# multipreamp-1.net
KiCad netlist of a schematic drawn in EAGLE
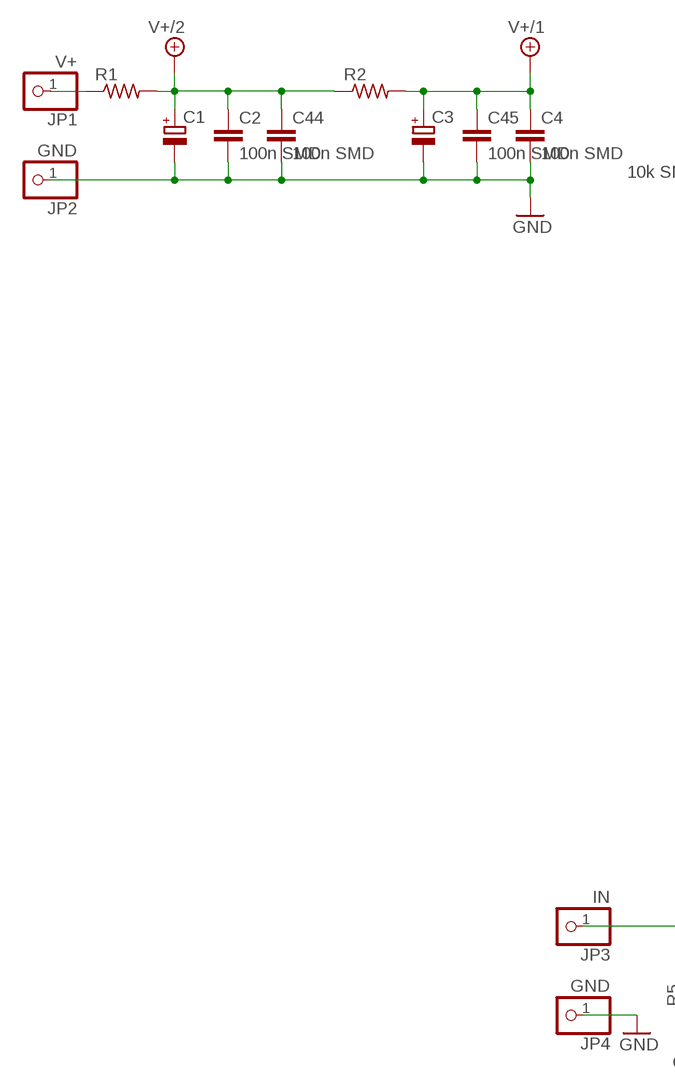
[diagram p0: schematic, sheet 1, part 1 of 2]
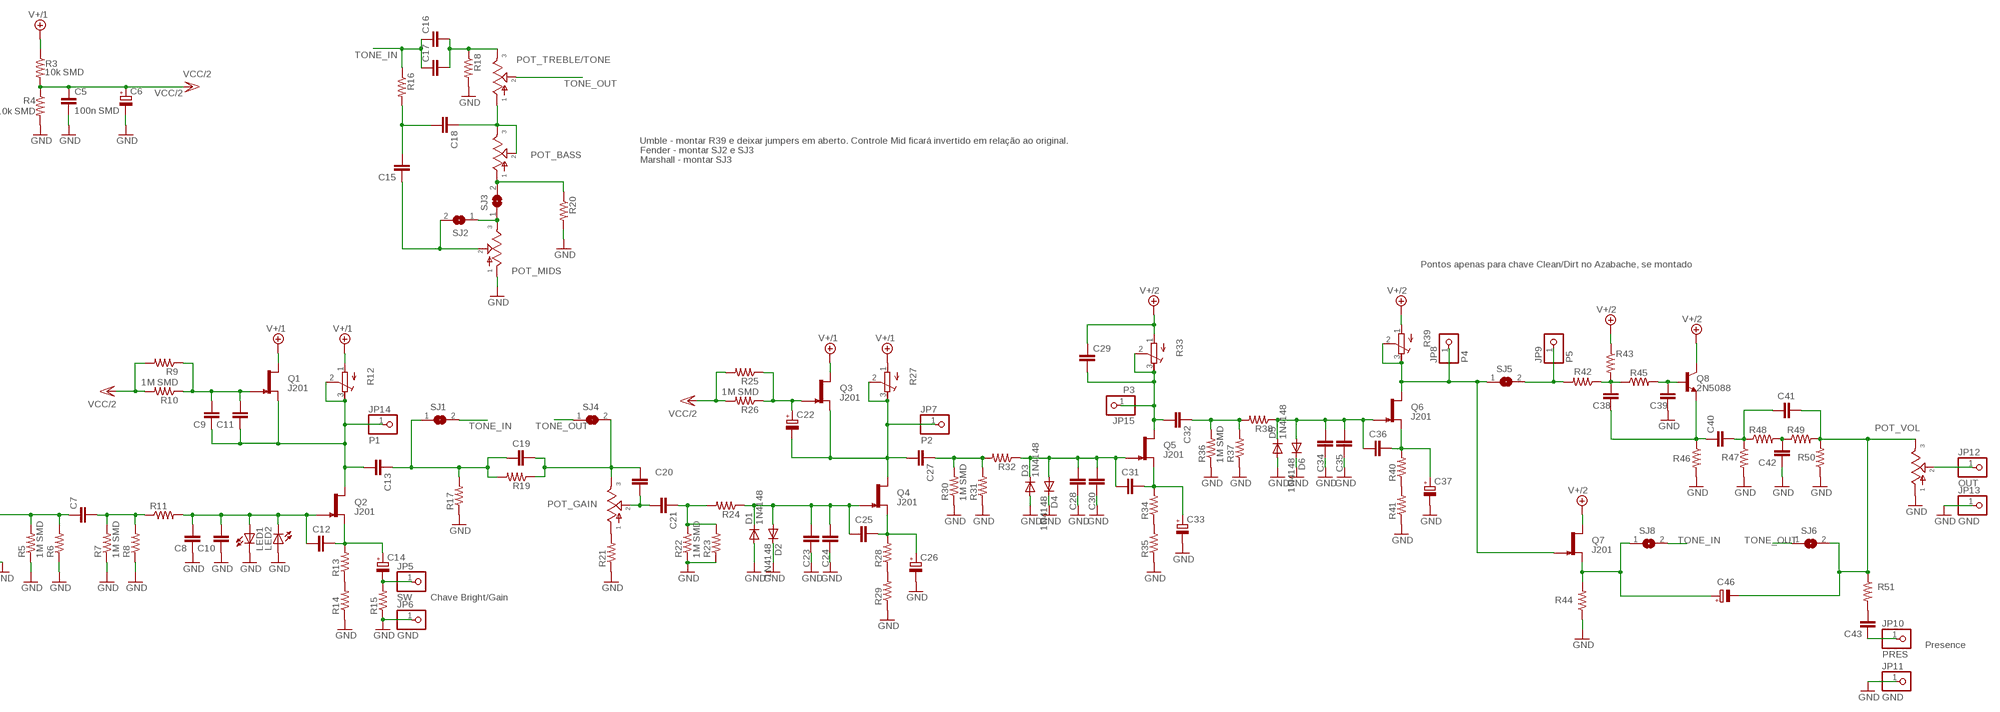
[diagram p1: schematic, sheet 1, part 2 of 2]

(export (version "E")
  (design (tool "Eeschema 10.0.6"))
  (components
    (comp (ref "C1")
      (value "CPOL-EUE2.5-6")
      (footprint "eagle-import:E2,5-6")
      (libsource (lib "eagle-import") (part "CPOL-EUE2.5-6"))
    )
    (comp (ref "C2")
      (value "100n SMD")
      (footprint "eagle-import:C0805")
      (libsource (lib "eagle-import") (part "C-EUC0805"))
    )
    (comp (ref "C3")
      (value "CPOL-EUE2.5-6")
      (footprint "eagle-import:E2,5-6")
      (libsource (lib "eagle-import") (part "CPOL-EUE2.5-6"))
    )
    (comp (ref "C4")
      (value "100n SMD")
      (footprint "eagle-import:C0805")
      (libsource (lib "eagle-import") (part "C-EUC0805"))
    )
    (comp (ref "C5")
      (value "100n SMD")
      (footprint "eagle-import:C0805")
      (libsource (lib "eagle-import") (part "C-EUC0805"))
    )
    (comp (ref "C6")
      (value "CPOL-EUE2.5-6")
      (footprint "eagle-import:E2,5-6")
      (libsource (lib "eagle-import") (part "CPOL-EUE2.5-6"))
    )
    (comp (ref "C7")
      (value "C-EU050-025X075")
      (footprint "eagle-import:C050-025X075")
      (libsource (lib "eagle-import") (part "C-EU050-025X075"))
    )
    (comp (ref "C8")
      (value "C-EU025-025X050")
      (footprint "eagle-import:C025-025X050")
      (libsource (lib "eagle-import") (part "C-EU025-025X050"))
    )
    (comp (ref "C9")
      (value "C-EU025-025X050")
      (footprint "eagle-import:C025-025X050")
      (libsource (lib "eagle-import") (part "C-EU025-025X050"))
    )
    (comp (ref "C10")
      (value "C-EU025-025X050")
      (footprint "eagle-import:C025-025X050")
      (libsource (lib "eagle-import") (part "C-EU025-025X050"))
    )
    (comp (ref "C11")
      (value "C-EU025-025X050")
      (footprint "eagle-import:C025-025X050")
      (libsource (lib "eagle-import") (part "C-EU025-025X050"))
    )
    (comp (ref "C12")
      (value "C-EU025-025X050")
      (footprint "eagle-import:C025-025X050")
      (libsource (lib "eagle-import") (part "C-EU025-025X050"))
    )
    (comp (ref "C13")
      (value "C-EU050-025X075")
      (footprint "eagle-import:C050-025X075")
      (libsource (lib "eagle-import") (part "C-EU050-025X075"))
    )
    (comp (ref "C14")
      (value "CPOL-EUE2.5-6")
      (footprint "eagle-import:E2,5-6")
      (libsource (lib "eagle-import") (part "CPOL-EUE2.5-6"))
    )
    (comp (ref "C15")
      (value "C-EU050-025X075")
      (footprint "eagle-import:C050-025X075")
      (libsource (lib "eagle-import") (part "C-EU050-025X075"))
    )
    (comp (ref "C16")
      (value "C-EU025-025X050")
      (footprint "eagle-import:C025-025X050")
      (libsource (lib "eagle-import") (part "C-EU025-025X050"))
    )
    (comp (ref "C17")
      (value "C-EU025-025X050")
      (footprint "eagle-import:C025-025X050")
      (libsource (lib "eagle-import") (part "C-EU025-025X050"))
    )
    (comp (ref "C18")
      (value "C-EU050-025X075")
      (footprint "eagle-import:C050-025X075")
      (libsource (lib "eagle-import") (part "C-EU050-025X075"))
    )
    (comp (ref "C19")
      (value "C-EU050-025X075")
      (footprint "eagle-import:C050-025X075")
      (libsource (lib "eagle-import") (part "C-EU050-025X075"))
    )
    (comp (ref "C20")
      (value "C-EU025-025X050")
      (footprint "eagle-import:C025-025X050")
      (libsource (lib "eagle-import") (part "C-EU025-025X050"))
    )
    (comp (ref "C21")
      (value "C-EU050-025X075")
      (footprint "eagle-import:C050-025X075")
      (libsource (lib "eagle-import") (part "C-EU050-025X075"))
    )
    (comp (ref "C22")
      (value "CPOL-EUE2.5-6")
      (footprint "eagle-import:E2,5-6")
      (libsource (lib "eagle-import") (part "CPOL-EUE2.5-6"))
    )
    (comp (ref "C23")
      (value "C-EU025-025X050")
      (footprint "eagle-import:C025-025X050")
      (libsource (lib "eagle-import") (part "C-EU025-025X050"))
    )
    (comp (ref "C24")
      (value "C-EU025-025X050")
      (footprint "eagle-import:C025-025X050")
      (libsource (lib "eagle-import") (part "C-EU025-025X050"))
    )
    (comp (ref "C25")
      (value "C-EU025-025X050")
      (footprint "eagle-import:C025-025X050")
      (libsource (lib "eagle-import") (part "C-EU025-025X050"))
    )
    (comp (ref "C26")
      (value "CPOL-EUE2.5-6")
      (footprint "eagle-import:E2,5-6")
      (libsource (lib "eagle-import") (part "CPOL-EUE2.5-6"))
    )
    (comp (ref "C27")
      (value "C-EU050-025X075")
      (footprint "eagle-import:C050-025X075")
      (libsource (lib "eagle-import") (part "C-EU050-025X075"))
    )
    (comp (ref "C28")
      (value "C-EU025-025X050")
      (footprint "eagle-import:C025-025X050")
      (libsource (lib "eagle-import") (part "C-EU025-025X050"))
    )
    (comp (ref "C29")
      (value "C-EU050-025X075")
      (footprint "eagle-import:C050-025X075")
      (libsource (lib "eagle-import") (part "C-EU050-025X075"))
    )
    (comp (ref "C30")
      (value "C-EU025-025X050")
      (footprint "eagle-import:C025-025X050")
      (libsource (lib "eagle-import") (part "C-EU025-025X050"))
    )
    (comp (ref "C31")
      (value "C-EU025-025X050")
      (footprint "eagle-import:C025-025X050")
      (libsource (lib "eagle-import") (part "C-EU025-025X050"))
    )
    (comp (ref "C32")
      (value "C-EU050-025X075")
      (footprint "eagle-import:C050-025X075")
      (libsource (lib "eagle-import") (part "C-EU050-025X075"))
    )
    (comp (ref "C33")
      (value "CPOL-EUE2.5-6")
      (footprint "eagle-import:E2,5-6")
      (libsource (lib "eagle-import") (part "CPOL-EUE2.5-6"))
    )
    (comp (ref "C34")
      (value "C-EU025-025X050")
      (footprint "eagle-import:C025-025X050")
      (libsource (lib "eagle-import") (part "C-EU025-025X050"))
    )
    (comp (ref "C35")
      (value "C-EU025-025X050")
      (footprint "eagle-import:C025-025X050")
      (libsource (lib "eagle-import") (part "C-EU025-025X050"))
    )
    (comp (ref "C36")
      (value "C-EU025-025X050")
      (footprint "eagle-import:C025-025X050")
      (libsource (lib "eagle-import") (part "C-EU025-025X050"))
    )
    (comp (ref "C37")
      (value "CPOL-EUE2.5-6")
      (footprint "eagle-import:E2,5-6")
      (libsource (lib "eagle-import") (part "CPOL-EUE2.5-6"))
    )
    (comp (ref "C38")
      (value "C-EU050-025X075")
      (footprint "eagle-import:C050-025X075")
      (libsource (lib "eagle-import") (part "C-EU050-025X075"))
    )
    (comp (ref "C39")
      (value "C-EU025-025X050")
      (footprint "eagle-import:C025-025X050")
      (libsource (lib "eagle-import") (part "C-EU025-025X050"))
    )
    (comp (ref "C40")
      (value "C-EU050-025X075")
      (footprint "eagle-import:C050-025X075")
      (libsource (lib "eagle-import") (part "C-EU050-025X075"))
    )
    (comp (ref "C41")
      (value "C-EU050-025X075")
      (footprint "eagle-import:C050-025X075")
      (libsource (lib "eagle-import") (part "C-EU050-025X075"))
    )
    (comp (ref "C42")
      (value "C-EU050-025X075")
      (footprint "eagle-import:C050-025X075")
      (libsource (lib "eagle-import") (part "C-EU050-025X075"))
    )
    (comp (ref "C43")
      (value "C-EU050-025X075")
      (footprint "eagle-import:C050-025X075")
      (libsource (lib "eagle-import") (part "C-EU050-025X075"))
    )
    (comp (ref "C44")
      (value "100n SMD")
      (footprint "eagle-import:C0805")
      (libsource (lib "eagle-import") (part "C-EUC0805"))
    )
    (comp (ref "C45")
      (value "100n SMD")
      (footprint "eagle-import:C0805")
      (libsource (lib "eagle-import") (part "C-EUC0805"))
    )
    (comp (ref "C46")
      (value "CPOL-EUE2.5-6")
      (footprint "eagle-import:E2,5-6")
      (libsource (lib "eagle-import") (part "CPOL-EUE2.5-6"))
    )
    (comp (ref "D1")
      (value "1N4148")
      (footprint "eagle-import:DO35-7")
      (libsource (lib "eagle-import") (part "1N4148DO35-7"))
    )
    (comp (ref "D2")
      (value "1N4148")
      (footprint "eagle-import:DO35-7")
      (libsource (lib "eagle-import") (part "1N4148DO35-7"))
    )
    (comp (ref "D3")
      (value "1N4148")
      (footprint "eagle-import:DO35-7")
      (libsource (lib "eagle-import") (part "1N4148DO35-7"))
    )
    (comp (ref "D4")
      (value "1N4148")
      (footprint "eagle-import:DO35-7")
      (libsource (lib "eagle-import") (part "1N4148DO35-7"))
    )
    (comp (ref "D5")
      (value "1N4148")
      (footprint "eagle-import:DO35-7")
      (libsource (lib "eagle-import") (part "1N4148DO35-7"))
    )
    (comp (ref "D6")
      (value "1N4148")
      (footprint "eagle-import:DO35-7")
      (libsource (lib "eagle-import") (part "1N4148DO35-7"))
    )
    (comp (ref "JP1")
      (value "V+")
      (footprint "eagle-import:1X01")
      (libsource (lib "eagle-import") (part "PINHD-1X1"))
    )
    (comp (ref "JP2")
      (value "GND")
      (footprint "eagle-import:1X01")
      (libsource (lib "eagle-import") (part "PINHD-1X1"))
    )
    (comp (ref "JP3")
      (value "IN")
      (footprint "eagle-import:1X01")
      (libsource (lib "eagle-import") (part "PINHD-1X1"))
    )
    (comp (ref "JP4")
      (value "GND")
      (footprint "eagle-import:1X01")
      (libsource (lib "eagle-import") (part "PINHD-1X1"))
    )
    (comp (ref "JP5")
      (value "SW")
      (footprint "eagle-import:1X01")
      (libsource (lib "eagle-import") (part "PINHD-1X1"))
    )
    (comp (ref "JP6")
      (value "GND")
      (footprint "eagle-import:1X01")
      (libsource (lib "eagle-import") (part "PINHD-1X1"))
    )
    (comp (ref "JP7")
      (value "P2")
      (footprint "eagle-import:1X01")
      (libsource (lib "eagle-import") (part "PINHD-1X1"))
    )
    (comp (ref "JP8")
      (value "P4")
      (footprint "eagle-import:1X01")
      (libsource (lib "eagle-import") (part "PINHD-1X1"))
    )
    (comp (ref "JP9")
      (value "P5")
      (footprint "eagle-import:1X01")
      (libsource (lib "eagle-import") (part "PINHD-1X1"))
    )
    (comp (ref "JP10")
      (value "PRES")
      (footprint "eagle-import:1X01")
      (libsource (lib "eagle-import") (part "PINHD-1X1"))
    )
    (comp (ref "JP11")
      (value "GND")
      (footprint "eagle-import:1X01")
      (libsource (lib "eagle-import") (part "PINHD-1X1"))
    )
    (comp (ref "JP12")
      (value "OUT")
      (footprint "eagle-import:1X01")
      (libsource (lib "eagle-import") (part "PINHD-1X1"))
    )
    (comp (ref "JP13")
      (value "GND")
      (footprint "eagle-import:1X01")
      (libsource (lib "eagle-import") (part "PINHD-1X1"))
    )
    (comp (ref "JP14")
      (value "P1")
      (footprint "eagle-import:1X01")
      (libsource (lib "eagle-import") (part "PINHD-1X1"))
    )
    (comp (ref "JP15")
      (value "P3")
      (footprint "eagle-import:1X01")
      (libsource (lib "eagle-import") (part "PINHD-1X1"))
    )
    (comp (ref "LED1")
      (value "LED3MM")
      (footprint "eagle-import:LED3MM")
      (libsource (lib "eagle-import") (part "LED3MM"))
    )
    (comp (ref "LED2")
      (value "LED3MM")
      (footprint "eagle-import:LED3MM")
      (libsource (lib "eagle-import") (part "LED3MM"))
    )
    (comp (ref "POT_BASS")
      (value "POTPCB")
      (footprint "eagle-import:16MM-PCB-MOUNT")
      (libsource (lib "eagle-import") (part "POTPCB"))
    )
    (comp (ref "POT_GAIN")
      (value "POTPCB")
      (footprint "eagle-import:16MM-PCB-MOUNT")
      (libsource (lib "eagle-import") (part "POTPCB"))
    )
    (comp (ref "POT_MIDS")
      (value "POTPCB")
      (footprint "eagle-import:16MM-PCB-MOUNT")
      (libsource (lib "eagle-import") (part "POTPCB"))
    )
    (comp (ref "POT_TREBLE/TONE")
      (value "POTPCB")
      (footprint "eagle-import:16MM-PCB-MOUNT")
      (libsource (lib "eagle-import") (part "POTPCB"))
    )
    (comp (ref "POT_VOL")
      (value "POTPCB")
      (footprint "eagle-import:16MM-PCB-MOUNT")
      (libsource (lib "eagle-import") (part "POTPCB"))
    )
    (comp (ref "Q1")
      (value "J201")
      (footprint "eagle-import:TO92-")
      (libsource (lib "eagle-import") (part "J201"))
    )
    (comp (ref "Q2")
      (value "J201")
      (footprint "eagle-import:TO92-")
      (libsource (lib "eagle-import") (part "J201"))
    )
    (comp (ref "Q3")
      (value "J201")
      (footprint "eagle-import:TO92-")
      (libsource (lib "eagle-import") (part "J201"))
    )
    (comp (ref "Q4")
      (value "J201")
      (footprint "eagle-import:TO92-")
      (libsource (lib "eagle-import") (part "J201"))
    )
    (comp (ref "Q5")
      (value "J201")
      (footprint "eagle-import:TO92-")
      (libsource (lib "eagle-import") (part "J201"))
    )
    (comp (ref "Q6")
      (value "J201")
      (footprint "eagle-import:TO92-")
      (libsource (lib "eagle-import") (part "J201"))
    )
    (comp (ref "Q7")
      (value "J201")
      (footprint "eagle-import:TO92-")
      (libsource (lib "eagle-import") (part "J201"))
    )
    (comp (ref "Q8")
      (value "2N5088")
      (footprint "eagle-import:TO92-")
      (libsource (lib "eagle-import") (part "2N5088"))
    )
    (comp (ref "R1")
      (value "R-US_0207/7")
      (footprint "eagle-import:0207_7")
      (libsource (lib "eagle-import") (part "R-US_0207/7"))
    )
    (comp (ref "R2")
      (value "R-US_0207/7")
      (footprint "eagle-import:0207_7")
      (libsource (lib "eagle-import") (part "R-US_0207/7"))
    )
    (comp (ref "R3")
      (value "10k SMD")
      (footprint "eagle-import:R0805")
      (libsource (lib "eagle-import") (part "R-US_R0805"))
    )
    (comp (ref "R4")
      (value "10k SMD")
      (footprint "eagle-import:R0805")
      (libsource (lib "eagle-import") (part "R-US_R0805"))
    )
    (comp (ref "R5")
      (value "1M SMD")
      (footprint "eagle-import:R0805")
      (libsource (lib "eagle-import") (part "R-US_R0805"))
    )
    (comp (ref "R6")
      (value "R-US_0207/2V")
      (footprint "eagle-import:0207_2V")
      (libsource (lib "eagle-import") (part "R-US_0207/2V"))
    )
    (comp (ref "R7")
      (value "1M SMD")
      (footprint "eagle-import:R0805")
      (libsource (lib "eagle-import") (part "R-US_R0805"))
    )
    (comp (ref "R8")
      (value "R-US_0207/2V")
      (footprint "eagle-import:0207_2V")
      (libsource (lib "eagle-import") (part "R-US_0207/2V"))
    )
    (comp (ref "R9")
      (value "R-US_0207/5V")
      (footprint "eagle-import:0207_5V")
      (libsource (lib "eagle-import") (part "R-US_0207/5V"))
    )
    (comp (ref "R10")
      (value "1M SMD")
      (footprint "eagle-import:R0805")
      (libsource (lib "eagle-import") (part "R-US_R0805"))
    )
    (comp (ref "R11")
      (value "R-US_0207/7")
      (footprint "eagle-import:0207_7")
      (libsource (lib "eagle-import") (part "R-US_0207/7"))
    )
    (comp (ref "R12")
      (value "R-TRIMM3296W")
      (footprint "eagle-import:RTRIM3296W")
      (libsource (lib "eagle-import") (part "R-TRIMM3296W"))
    )
    (comp (ref "R13")
      (value "R-US_0207/7")
      (footprint "eagle-import:0207_7")
      (libsource (lib "eagle-import") (part "R-US_0207/7"))
    )
    (comp (ref "R14")
      (value "R-US_0207/7")
      (footprint "eagle-import:0207_7")
      (libsource (lib "eagle-import") (part "R-US_0207/7"))
    )
    (comp (ref "R15")
      (value "R-US_0207/7")
      (footprint "eagle-import:0207_7")
      (libsource (lib "eagle-import") (part "R-US_0207/7"))
    )
    (comp (ref "R16")
      (value "R-US_0207/7")
      (footprint "eagle-import:0207_7")
      (libsource (lib "eagle-import") (part "R-US_0207/7"))
    )
    (comp (ref "R17")
      (value "R-US_0207/7")
      (footprint "eagle-import:0207_7")
      (libsource (lib "eagle-import") (part "R-US_0207/7"))
    )
    (comp (ref "R18")
      (value "R-US_0207/7")
      (footprint "eagle-import:0207_7")
      (libsource (lib "eagle-import") (part "R-US_0207/7"))
    )
    (comp (ref "R19")
      (value "R-US_0207/7")
      (footprint "eagle-import:0207_7")
      (libsource (lib "eagle-import") (part "R-US_0207/7"))
    )
    (comp (ref "R20")
      (value "R-US_0207/7")
      (footprint "eagle-import:0207_7")
      (libsource (lib "eagle-import") (part "R-US_0207/7"))
    )
    (comp (ref "R21")
      (value "R-US_R0805")
      (footprint "eagle-import:R0805")
      (libsource (lib "eagle-import") (part "R-US_R0805"))
    )
    (comp (ref "R22")
      (value "1M SMD")
      (footprint "eagle-import:R0805")
      (libsource (lib "eagle-import") (part "R-US_R0805"))
    )
    (comp (ref "R23")
      (value "R-US_0207/7")
      (footprint "eagle-import:0207_7")
      (libsource (lib "eagle-import") (part "R-US_0207/7"))
    )
    (comp (ref "R24")
      (value "R-US_0207/7")
      (footprint "eagle-import:0207_7")
      (libsource (lib "eagle-import") (part "R-US_0207/7"))
    )
    (comp (ref "R25")
      (value "R-US_0207/5V")
      (footprint "eagle-import:0207_5V")
      (libsource (lib "eagle-import") (part "R-US_0207/5V"))
    )
    (comp (ref "R26")
      (value "1M SMD")
      (footprint "eagle-import:R0805")
      (libsource (lib "eagle-import") (part "R-US_R0805"))
    )
    (comp (ref "R27")
      (value "R-TRIMM3296W")
      (footprint "eagle-import:RTRIM3296W")
      (libsource (lib "eagle-import") (part "R-TRIMM3296W"))
    )
    (comp (ref "R28")
      (value "R-US_0207/7")
      (footprint "eagle-import:0207_7")
      (libsource (lib "eagle-import") (part "R-US_0207/7"))
    )
    (comp (ref "R29")
      (value "R-US_0207/7")
      (footprint "eagle-import:0207_7")
      (libsource (lib "eagle-import") (part "R-US_0207/7"))
    )
    (comp (ref "R30")
      (value "1M SMD")
      (footprint "eagle-import:R0805")
      (libsource (lib "eagle-import") (part "R-US_R0805"))
    )
    (comp (ref "R31")
      (value "R-US_0207/7")
      (footprint "eagle-import:0207_7")
      (libsource (lib "eagle-import") (part "R-US_0207/7"))
    )
    (comp (ref "R32")
      (value "R-US_0207/7")
      (footprint "eagle-import:0207_7")
      (libsource (lib "eagle-import") (part "R-US_0207/7"))
    )
    (comp (ref "R33")
      (value "R-TRIMM3296W")
      (footprint "eagle-import:RTRIM3296W")
      (libsource (lib "eagle-import") (part "R-TRIMM3296W"))
    )
    (comp (ref "R34")
      (value "R-US_0207/7")
      (footprint "eagle-import:0207_7")
      (libsource (lib "eagle-import") (part "R-US_0207/7"))
    )
    (comp (ref "R35")
      (value "R-US_0207/7")
      (footprint "eagle-import:0207_7")
      (libsource (lib "eagle-import") (part "R-US_0207/7"))
    )
    (comp (ref "R36")
      (value "1M SMD")
      (footprint "eagle-import:R0805")
      (libsource (lib "eagle-import") (part "R-US_R0805"))
    )
    (comp (ref "R37")
      (value "R-US_0207/7")
      (footprint "eagle-import:0207_7")
      (libsource (lib "eagle-import") (part "R-US_0207/7"))
    )
    (comp (ref "R38")
      (value "R-US_0207/7")
      (footprint "eagle-import:0207_7")
      (libsource (lib "eagle-import") (part "R-US_0207/7"))
    )
    (comp (ref "R39")
      (value "R-TRIMM3296W")
      (footprint "eagle-import:RTRIM3296W")
      (libsource (lib "eagle-import") (part "R-TRIMM3296W"))
    )
    (comp (ref "R40")
      (value "R-US_0207/7")
      (footprint "eagle-import:0207_7")
      (libsource (lib "eagle-import") (part "R-US_0207/7"))
    )
    (comp (ref "R41")
      (value "R-US_0207/7")
      (footprint "eagle-import:0207_7")
      (libsource (lib "eagle-import") (part "R-US_0207/7"))
    )
    (comp (ref "R42")
      (value "R-US_0207/7")
      (footprint "eagle-import:0207_7")
      (libsource (lib "eagle-import") (part "R-US_0207/7"))
    )
    (comp (ref "R43")
      (value "R-US_0207/7")
      (footprint "eagle-import:0207_7")
      (libsource (lib "eagle-import") (part "R-US_0207/7"))
    )
    (comp (ref "R44")
      (value "R-US_0207/7")
      (footprint "eagle-import:0207_7")
      (libsource (lib "eagle-import") (part "R-US_0207/7"))
    )
    (comp (ref "R45")
      (value "R-US_0207/7")
      (footprint "eagle-import:0207_7")
      (libsource (lib "eagle-import") (part "R-US_0207/7"))
    )
    (comp (ref "R46")
      (value "R-US_0207/7")
      (footprint "eagle-import:0207_7")
      (libsource (lib "eagle-import") (part "R-US_0207/7"))
    )
    (comp (ref "R47")
      (value "R-US_0207/7")
      (footprint "eagle-import:0207_7")
      (libsource (lib "eagle-import") (part "R-US_0207/7"))
    )
    (comp (ref "R48")
      (value "R-US_0207/7")
      (footprint "eagle-import:0207_7")
      (libsource (lib "eagle-import") (part "R-US_0207/7"))
    )
    (comp (ref "R49")
      (value "R-US_0207/7")
      (footprint "eagle-import:0207_7")
      (libsource (lib "eagle-import") (part "R-US_0207/7"))
    )
    (comp (ref "R50")
      (value "R-US_0207/7")
      (footprint "eagle-import:0207_7")
      (libsource (lib "eagle-import") (part "R-US_0207/7"))
    )
    (comp (ref "R51")
      (value "R-US_0207/7")
      (footprint "eagle-import:0207_7")
      (libsource (lib "eagle-import") (part "R-US_0207/7"))
    )
    (comp (ref "SJ1") (value "SJ") (footprint "eagle-import:SJ") (libsource (lib "eagle-import") (part "SJ")))
    (comp (ref "SJ2") (value "SJ") (footprint "eagle-import:SJ") (libsource (lib "eagle-import") (part "SJ")))
    (comp (ref "SJ3") (value "SJ") (footprint "eagle-import:SJ") (libsource (lib "eagle-import") (part "SJ")))
    (comp (ref "SJ4") (value "SJ") (footprint "eagle-import:SJ") (libsource (lib "eagle-import") (part "SJ")))
    (comp (ref "SJ5") (value "SJ") (footprint "eagle-import:SJ") (libsource (lib "eagle-import") (part "SJ")))
    (comp (ref "SJ6") (value "SJ") (footprint "eagle-import:SJ") (libsource (lib "eagle-import") (part "SJ")))
    (comp (ref "SJ8") (value "SJ") (footprint "eagle-import:SJ") (libsource (lib "eagle-import") (part "SJ")))
  )
  (nets
    (net (code "1") (name "/TONE_IN") (class "Default")
      (node (ref "C16") (pin "1") (pinfunction "1_1") (pintype "passive"))
      (node (ref "C17") (pin "1") (pinfunction "1_1") (pintype "passive"))
      (node (ref "R16") (pin "1") (pinfunction "1_1") (pintype "passive"))
      (node (ref "SJ1") (pin "2") (pinfunction "2_2") (pintype "passive"))
      (node (ref "SJ8") (pin "2") (pinfunction "2_2") (pintype "passive"))
    )
    (net (code "2") (name "/TONE_OUT") (class "Default")
      (node (ref "POT_TREBLE/TONE") (pin "2") (pinfunction "2_2") (pintype "passive"))
      (node (ref "SJ4") (pin "1") (pinfunction "1_1") (pintype "passive"))
      (node (ref "SJ6") (pin "1") (pinfunction "1_1") (pintype "passive"))
    )
    (net (code "3") (name "GND") (class "Default")
      (node (ref "C1") (pin "-") (pinfunction "-_-") (pintype "passive"))
      (node (ref "C10") (pin "1") (pinfunction "1_1") (pintype "passive"))
      (node (ref "C2") (pin "2") (pinfunction "2_2") (pintype "passive"))
      (node (ref "C23") (pin "1") (pinfunction "1_1") (pintype "passive"))
      (node (ref "C24") (pin "1") (pinfunction "1_1") (pintype "passive"))
      (node (ref "C26") (pin "-") (pinfunction "-_-") (pintype "passive"))
      (node (ref "C28") (pin "1") (pinfunction "1_1") (pintype "passive"))
      (node (ref "C3") (pin "-") (pinfunction "-_-") (pintype "passive"))
      (node (ref "C30") (pin "1") (pinfunction "1_1") (pintype "passive"))
      (node (ref "C33") (pin "-") (pinfunction "-_-") (pintype "passive"))
      (node (ref "C34") (pin "1") (pinfunction "1_1") (pintype "passive"))
      (node (ref "C35") (pin "1") (pinfunction "1_1") (pintype "passive"))
      (node (ref "C37") (pin "-") (pinfunction "-_-") (pintype "passive"))
      (node (ref "C39") (pin "1") (pinfunction "1_1") (pintype "passive"))
      (node (ref "C4") (pin "2") (pinfunction "2_2") (pintype "passive"))
      (node (ref "C42") (pin "1") (pinfunction "1_1") (pintype "passive"))
      (node (ref "C44") (pin "2") (pinfunction "2_2") (pintype "passive"))
      (node (ref "C45") (pin "2") (pinfunction "2_2") (pintype "passive"))
      (node (ref "C5") (pin "2") (pinfunction "2_2") (pintype "passive"))
      (node (ref "C6") (pin "-") (pinfunction "-_-") (pintype "passive"))
      (node (ref "C8") (pin "1") (pinfunction "1_1") (pintype "passive"))
      (node (ref "D1") (pin "A") (pinfunction "A_A") (pintype "passive"))
      (node (ref "D2") (pin "C") (pinfunction "C_C") (pintype "passive"))
      (node (ref "D3") (pin "A") (pinfunction "A_A") (pintype "passive"))
      (node (ref "D4") (pin "C") (pinfunction "C_C") (pintype "passive"))
      (node (ref "D5") (pin "A") (pinfunction "A_A") (pintype "passive"))
      (node (ref "D6") (pin "C") (pinfunction "C_C") (pintype "passive"))
      (node (ref "JP11") (pin "1") (pinfunction "1_1") (pintype "passive"))
      (node (ref "JP13") (pin "1") (pinfunction "1_1") (pintype "passive"))
      (node (ref "JP2") (pin "1") (pinfunction "1_1") (pintype "passive"))
      (node (ref "JP4") (pin "1") (pinfunction "1_1") (pintype "passive"))
      (node (ref "JP6") (pin "1") (pinfunction "1_1") (pintype "passive"))
      (node (ref "LED1") (pin "K") (pinfunction "C_K") (pintype "passive"))
      (node (ref "LED2") (pin "A") (pinfunction "A_A") (pintype "passive"))
      (node (ref "POT_MIDS") (pin "1") (pinfunction "1_1") (pintype "passive"))
      (node (ref "POT_VOL") (pin "1") (pinfunction "1_1") (pintype "passive"))
      (node (ref "R14") (pin "1") (pinfunction "1_1") (pintype "passive"))
      (node (ref "R15") (pin "1") (pinfunction "1_1") (pintype "passive"))
      (node (ref "R17") (pin "1") (pinfunction "1_1") (pintype "passive"))
      (node (ref "R18") (pin "2") (pinfunction "2_2") (pintype "passive"))
      (node (ref "R20") (pin "2") (pinfunction "2_2") (pintype "passive"))
      (node (ref "R21") (pin "1") (pinfunction "1_1") (pintype "passive"))
      (node (ref "R22") (pin "1") (pinfunction "1_1") (pintype "passive"))
      (node (ref "R23") (pin "1") (pinfunction "1_1") (pintype "passive"))
      (node (ref "R29") (pin "1") (pinfunction "1_1") (pintype "passive"))
      (node (ref "R30") (pin "1") (pinfunction "1_1") (pintype "passive"))
      (node (ref "R31") (pin "1") (pinfunction "1_1") (pintype "passive"))
      (node (ref "R35") (pin "1") (pinfunction "1_1") (pintype "passive"))
      (node (ref "R36") (pin "1") (pinfunction "1_1") (pintype "passive"))
      (node (ref "R37") (pin "1") (pinfunction "1_1") (pintype "passive"))
      (node (ref "R4") (pin "2") (pinfunction "2_2") (pintype "passive"))
      (node (ref "R41") (pin "1") (pinfunction "1_1") (pintype "passive"))
      (node (ref "R44") (pin "1") (pinfunction "1_1") (pintype "passive"))
      (node (ref "R46") (pin "2") (pinfunction "2_2") (pintype "passive"))
      (node (ref "R47") (pin "2") (pinfunction "2_2") (pintype "passive"))
      (node (ref "R5") (pin "1") (pinfunction "1_1") (pintype "passive"))
      (node (ref "R50") (pin "1") (pinfunction "1_1") (pintype "passive"))
      (node (ref "R6") (pin "1") (pinfunction "1_1") (pintype "passive"))
      (node (ref "R7") (pin "1") (pinfunction "1_1") (pintype "passive"))
      (node (ref "R8") (pin "1") (pinfunction "1_1") (pintype "passive"))
    )
    (net (code "4") (name "Net-(C7-Pad1)") (class "Default")
      (node (ref "C7") (pin "1") (pinfunction "1_1") (pintype "passive"))
      (node (ref "JP3") (pin "1") (pinfunction "1_1") (pintype "passive"))
      (node (ref "R5") (pin "2") (pinfunction "2_2") (pintype "passive"))
      (node (ref "R6") (pin "2") (pinfunction "2_2") (pintype "passive"))
    )
    (net (code "5") (name "Net-(C7-Pad2)") (class "Default")
      (node (ref "C7") (pin "2") (pinfunction "2_2") (pintype "passive"))
      (node (ref "R11") (pin "1") (pinfunction "1_1") (pintype "passive"))
      (node (ref "R7") (pin "2") (pinfunction "2_2") (pintype "passive"))
      (node (ref "R8") (pin "2") (pinfunction "2_2") (pintype "passive"))
    )
    (net (code "6") (name "Net-(C13-Pad1)") (class "Default")
      (node (ref "C13") (pin "1") (pinfunction "1_1") (pintype "passive"))
      (node (ref "C19") (pin "2") (pinfunction "2_2") (pintype "passive"))
      (node (ref "R17") (pin "2") (pinfunction "2_2") (pintype "passive"))
      (node (ref "R19") (pin "2") (pinfunction "2_2") (pintype "passive"))
      (node (ref "SJ1") (pin "1") (pinfunction "1_1") (pintype "passive"))
    )
    (net (code "7") (name "Net-(C14-Pad-)") (class "Default")
      (node (ref "C14") (pin "-") (pinfunction "-_-") (pintype "passive"))
      (node (ref "JP5") (pin "1") (pinfunction "1_1") (pintype "passive"))
      (node (ref "R15") (pin "2") (pinfunction "2_2") (pintype "passive"))
    )
    (net (code "8") (name "Net-(C15-Pad1)") (class "Default")
      (node (ref "C15") (pin "1") (pinfunction "1_1") (pintype "passive"))
      (node (ref "POT_MIDS") (pin "2") (pinfunction "2_2") (pintype "passive"))
      (node (ref "SJ2") (pin "2") (pinfunction "2_2") (pintype "passive"))
    )
    (net (code "9") (name "Net-(C15-Pad2)") (class "Default")
      (node (ref "C15") (pin "2") (pinfunction "2_2") (pintype "passive"))
      (node (ref "C18") (pin "2") (pinfunction "2_2") (pintype "passive"))
      (node (ref "R16") (pin "2") (pinfunction "2_2") (pintype "passive"))
    )
    (net (code "10") (name "Net-(C16-Pad2)") (class "Default")
      (node (ref "C16") (pin "2") (pinfunction "2_2") (pintype "passive"))
      (node (ref "C17") (pin "2") (pinfunction "2_2") (pintype "passive"))
      (node (ref "POT_TREBLE/TONE") (pin "3") (pinfunction "3_3") (pintype "passive"))
      (node (ref "R18") (pin "1") (pinfunction "1_1") (pintype "passive"))
    )
    (net (code "11") (name "Net-(C18-Pad1)") (class "Default")
      (node (ref "C18") (pin "1") (pinfunction "1_1") (pintype "passive"))
      (node (ref "POT_BASS") (pin "2") (pinfunction "2_2") (pintype "passive"))
      (node (ref "POT_BASS") (pin "3") (pinfunction "3_3") (pintype "passive"))
      (node (ref "POT_TREBLE/TONE") (pin "1") (pinfunction "1_1") (pintype "passive"))
    )
    (net (code "12") (name "Net-(C19-Pad1)") (class "Default")
      (node (ref "C19") (pin "1") (pinfunction "1_1") (pintype "passive"))
      (node (ref "C20") (pin "2") (pinfunction "2_2") (pintype "passive"))
      (node (ref "POT_GAIN") (pin "3") (pinfunction "3_3") (pintype "passive"))
      (node (ref "R19") (pin "1") (pinfunction "1_1") (pintype "passive"))
      (node (ref "SJ4") (pin "2") (pinfunction "2_2") (pintype "passive"))
    )
    (net (code "13") (name "Net-(C20-Pad1)") (class "Default")
      (node (ref "C20") (pin "1") (pinfunction "1_1") (pintype "passive"))
      (node (ref "C21") (pin "2") (pinfunction "2_2") (pintype "passive"))
      (node (ref "POT_GAIN") (pin "2") (pinfunction "2_2") (pintype "passive"))
    )
    (net (code "14") (name "Net-(C21-Pad1)") (class "Default")
      (node (ref "C21") (pin "1") (pinfunction "1_1") (pintype "passive"))
      (node (ref "R22") (pin "2") (pinfunction "2_2") (pintype "passive"))
      (node (ref "R23") (pin "2") (pinfunction "2_2") (pintype "passive"))
      (node (ref "R24") (pin "2") (pinfunction "2_2") (pintype "passive"))
    )
    (net (code "15") (name "Net-(C27-Pad1)") (class "Default")
      (node (ref "C27") (pin "1") (pinfunction "1_1") (pintype "passive"))
      (node (ref "R30") (pin "2") (pinfunction "2_2") (pintype "passive"))
      (node (ref "R31") (pin "2") (pinfunction "2_2") (pintype "passive"))
      (node (ref "R32") (pin "2") (pinfunction "2_2") (pintype "passive"))
    )
    (net (code "16") (name "Net-(C32-Pad1)") (class "Default")
      (node (ref "C32") (pin "1") (pinfunction "1_1") (pintype "passive"))
      (node (ref "R36") (pin "2") (pinfunction "2_2") (pintype "passive"))
      (node (ref "R37") (pin "2") (pinfunction "2_2") (pintype "passive"))
      (node (ref "R38") (pin "2") (pinfunction "2_2") (pintype "passive"))
    )
    (net (code "17") (name "Net-(C38-Pad1)") (class "Default")
      (node (ref "C38") (pin "1") (pinfunction "1_1") (pintype "passive"))
      (node (ref "R42") (pin "1") (pinfunction "1_1") (pintype "passive"))
      (node (ref "R43") (pin "2") (pinfunction "2_2") (pintype "passive"))
      (node (ref "R45") (pin "1") (pinfunction "1_1") (pintype "passive"))
    )
    (net (code "18") (name "Net-(C40-Pad2)") (class "Default")
      (node (ref "C40") (pin "2") (pinfunction "2_2") (pintype "passive"))
      (node (ref "C41") (pin "1") (pinfunction "1_1") (pintype "passive"))
      (node (ref "R47") (pin "1") (pinfunction "1_1") (pintype "passive"))
      (node (ref "R48") (pin "1") (pinfunction "1_1") (pintype "passive"))
    )
    (net (code "19") (name "Net-(C41-Pad2)") (class "Default")
      (node (ref "C41") (pin "2") (pinfunction "2_2") (pintype "passive"))
      (node (ref "C46") (pin "-") (pinfunction "-_-") (pintype "passive"))
      (node (ref "POT_VOL") (pin "3") (pinfunction "3_3") (pintype "passive"))
      (node (ref "R49") (pin "2") (pinfunction "2_2") (pintype "passive"))
      (node (ref "R50") (pin "2") (pinfunction "2_2") (pintype "passive"))
      (node (ref "R51") (pin "1") (pinfunction "1_1") (pintype "passive"))
      (node (ref "SJ6") (pin "2") (pinfunction "2_2") (pintype "passive"))
    )
    (net (code "20") (name "Net-(C42-Pad2)") (class "Default")
      (node (ref "C42") (pin "2") (pinfunction "2_2") (pintype "passive"))
      (node (ref "R48") (pin "2") (pinfunction "2_2") (pintype "passive"))
      (node (ref "R49") (pin "1") (pinfunction "1_1") (pintype "passive"))
    )
    (net (code "21") (name "Net-(C43-Pad1)") (class "Default")
      (node (ref "C43") (pin "1") (pinfunction "1_1") (pintype "passive"))
      (node (ref "JP10") (pin "1") (pinfunction "1_1") (pintype "passive"))
    )
    (net (code "22") (name "Net-(C43-Pad2)") (class "Default")
      (node (ref "C43") (pin "2") (pinfunction "2_2") (pintype "passive"))
      (node (ref "R51") (pin "2") (pinfunction "2_2") (pintype "passive"))
    )
    (net (code "23") (name "Net-(JP1-Pad1)") (class "Default")
      (node (ref "JP1") (pin "1") (pinfunction "1_1") (pintype "passive"))
      (node (ref "R1") (pin "1") (pinfunction "1_1") (pintype "passive"))
    )
    (net (code "24") (name "Net-(JP9-Pad1)") (class "Default")
      (node (ref "JP9") (pin "1") (pinfunction "1_1") (pintype "passive"))
      (node (ref "R42") (pin "2") (pinfunction "2_2") (pintype "passive"))
      (node (ref "SJ5") (pin "2") (pinfunction "2_2") (pintype "passive"))
    )
    (net (code "25") (name "Net-(JP12-Pad1)") (class "Default")
      (node (ref "JP12") (pin "1") (pinfunction "1_1") (pintype "passive"))
      (node (ref "POT_VOL") (pin "2") (pinfunction "2_2") (pintype "passive"))
    )
    (net (code "26") (name "Net-(LED2-C)") (class "Default")
      (node (ref "C10") (pin "2") (pinfunction "2_2") (pintype "passive"))
      (node (ref "C12") (pin "2") (pinfunction "2_2") (pintype "passive"))
      (node (ref "C8") (pin "2") (pinfunction "2_2") (pintype "passive"))
      (node (ref "LED1") (pin "A") (pinfunction "A_A") (pintype "passive"))
      (node (ref "LED2") (pin "K") (pinfunction "C_K") (pintype "passive"))
      (node (ref "Q2") (pin "1") (pinfunction "G_1") (pintype "passive"))
      (node (ref "R11") (pin "2") (pinfunction "2_2") (pintype "passive"))
    )
    (net (code "27") (name "Net-(POT_BASS-Pad1)") (class "Default")
      (node (ref "POT_BASS") (pin "1") (pinfunction "1_1") (pintype "passive"))
      (node (ref "R20") (pin "1") (pinfunction "1_1") (pintype "passive"))
      (node (ref "SJ3") (pin "2") (pinfunction "2_2") (pintype "passive"))
    )
    (net (code "28") (name "Net-(POT_GAIN-Pad1)") (class "Default")
      (node (ref "POT_GAIN") (pin "1") (pinfunction "1_1") (pintype "passive"))
      (node (ref "R21") (pin "2") (pinfunction "2_2") (pintype "passive"))
    )
    (net (code "29") (name "Net-(POT_MIDS-Pad3)") (class "Default")
      (node (ref "POT_MIDS") (pin "3") (pinfunction "3_3") (pintype "passive"))
      (node (ref "SJ2") (pin "1") (pinfunction "1_1") (pintype "passive"))
      (node (ref "SJ3") (pin "1") (pinfunction "1_1") (pintype "passive"))
    )
    (net (code "30") (name "Net-(Q1-G)") (class "Default")
      (node (ref "C11") (pin "2") (pinfunction "2_2") (pintype "passive"))
      (node (ref "C9") (pin "2") (pinfunction "2_2") (pintype "passive"))
      (node (ref "Q1") (pin "1") (pinfunction "G_1") (pintype "passive"))
      (node (ref "R10") (pin "1") (pinfunction "1_1") (pintype "passive"))
      (node (ref "R9") (pin "1") (pinfunction "1_1") (pintype "passive"))
    )
    (net (code "31") (name "Net-(Q1-S)") (class "Default")
      (node (ref "C11") (pin "1") (pinfunction "1_1") (pintype "passive"))
      (node (ref "C13") (pin "2") (pinfunction "2_2") (pintype "passive"))
      (node (ref "C9") (pin "1") (pinfunction "1_1") (pintype "passive"))
      (node (ref "JP14") (pin "1") (pinfunction "1_1") (pintype "passive"))
      (node (ref "Q1") (pin "2") (pinfunction "S_2") (pintype "passive"))
      (node (ref "Q2") (pin "3") (pinfunction "D_3") (pintype "passive"))
      (node (ref "R12") (pin "2") (pinfunction "S_2") (pintype "passive"))
      (node (ref "R12") (pin "3") (pinfunction "E_3") (pintype "passive"))
    )
    (net (code "32") (name "Net-(Q2-S)") (class "Default")
      (node (ref "C12") (pin "1") (pinfunction "1_1") (pintype "passive"))
      (node (ref "C14") (pin "+") (pinfunction "+_+") (pintype "passive"))
      (node (ref "Q2") (pin "2") (pinfunction "S_2") (pintype "passive"))
      (node (ref "R13") (pin "2") (pinfunction "2_2") (pintype "passive"))
    )
    (net (code "33") (name "Net-(Q3-G)") (class "Default")
      (node (ref "C22") (pin "+") (pinfunction "+_+") (pintype "passive"))
      (node (ref "Q3") (pin "1") (pinfunction "G_1") (pintype "passive"))
      (node (ref "R25") (pin "1") (pinfunction "1_1") (pintype "passive"))
      (node (ref "R26") (pin "1") (pinfunction "1_1") (pintype "passive"))
    )
    (net (code "34") (name "Net-(Q3-S)") (class "Default")
      (node (ref "C22") (pin "-") (pinfunction "-_-") (pintype "passive"))
      (node (ref "C27") (pin "2") (pinfunction "2_2") (pintype "passive"))
      (node (ref "JP7") (pin "1") (pinfunction "1_1") (pintype "passive"))
      (node (ref "Q3") (pin "2") (pinfunction "S_2") (pintype "passive"))
      (node (ref "Q4") (pin "3") (pinfunction "D_3") (pintype "passive"))
      (node (ref "R27") (pin "2") (pinfunction "S_2") (pintype "passive"))
      (node (ref "R27") (pin "3") (pinfunction "E_3") (pintype "passive"))
    )
    (net (code "35") (name "Net-(Q4-G)") (class "Default")
      (node (ref "C23") (pin "2") (pinfunction "2_2") (pintype "passive"))
      (node (ref "C24") (pin "2") (pinfunction "2_2") (pintype "passive"))
      (node (ref "C25") (pin "2") (pinfunction "2_2") (pintype "passive"))
      (node (ref "D1") (pin "C") (pinfunction "C_C") (pintype "passive"))
      (node (ref "D2") (pin "A") (pinfunction "A_A") (pintype "passive"))
      (node (ref "Q4") (pin "1") (pinfunction "G_1") (pintype "passive"))
      (node (ref "R24") (pin "1") (pinfunction "1_1") (pintype "passive"))
    )
    (net (code "36") (name "Net-(Q4-S)") (class "Default")
      (node (ref "C25") (pin "1") (pinfunction "1_1") (pintype "passive"))
      (node (ref "C26") (pin "+") (pinfunction "+_+") (pintype "passive"))
      (node (ref "Q4") (pin "2") (pinfunction "S_2") (pintype "passive"))
      (node (ref "R28") (pin "2") (pinfunction "2_2") (pintype "passive"))
    )
    (net (code "37") (name "Net-(Q5-D)") (class "Default")
      (node (ref "C29") (pin "2") (pinfunction "2_2") (pintype "passive"))
      (node (ref "C32") (pin "2") (pinfunction "2_2") (pintype "passive"))
      (node (ref "JP15") (pin "1") (pinfunction "1_1") (pintype "passive"))
      (node (ref "Q5") (pin "3") (pinfunction "D_3") (pintype "passive"))
      (node (ref "R33") (pin "2") (pinfunction "S_2") (pintype "passive"))
      (node (ref "R33") (pin "3") (pinfunction "E_3") (pintype "passive"))
    )
    (net (code "38") (name "Net-(Q5-G)") (class "Default")
      (node (ref "C28") (pin "2") (pinfunction "2_2") (pintype "passive"))
      (node (ref "C30") (pin "2") (pinfunction "2_2") (pintype "passive"))
      (node (ref "C31") (pin "2") (pinfunction "2_2") (pintype "passive"))
      (node (ref "D3") (pin "C") (pinfunction "C_C") (pintype "passive"))
      (node (ref "D4") (pin "A") (pinfunction "A_A") (pintype "passive"))
      (node (ref "Q5") (pin "1") (pinfunction "G_1") (pintype "passive"))
      (node (ref "R32") (pin "1") (pinfunction "1_1") (pintype "passive"))
    )
    (net (code "39") (name "Net-(Q5-S)") (class "Default")
      (node (ref "C31") (pin "1") (pinfunction "1_1") (pintype "passive"))
      (node (ref "C33") (pin "+") (pinfunction "+_+") (pintype "passive"))
      (node (ref "Q5") (pin "2") (pinfunction "S_2") (pintype "passive"))
      (node (ref "R34") (pin "2") (pinfunction "2_2") (pintype "passive"))
    )
    (net (code "40") (name "Net-(Q6-D)") (class "Default")
      (node (ref "JP8") (pin "1") (pinfunction "1_1") (pintype "passive"))
      (node (ref "Q6") (pin "3") (pinfunction "D_3") (pintype "passive"))
      (node (ref "Q7") (pin "1") (pinfunction "G_1") (pintype "passive"))
      (node (ref "R39") (pin "2") (pinfunction "S_2") (pintype "passive"))
      (node (ref "R39") (pin "3") (pinfunction "E_3") (pintype "passive"))
      (node (ref "SJ5") (pin "1") (pinfunction "1_1") (pintype "passive"))
    )
    (net (code "41") (name "Net-(Q6-G)") (class "Default")
      (node (ref "C34") (pin "2") (pinfunction "2_2") (pintype "passive"))
      (node (ref "C35") (pin "2") (pinfunction "2_2") (pintype "passive"))
      (node (ref "C36") (pin "2") (pinfunction "2_2") (pintype "passive"))
      (node (ref "D5") (pin "C") (pinfunction "C_C") (pintype "passive"))
      (node (ref "D6") (pin "A") (pinfunction "A_A") (pintype "passive"))
      (node (ref "Q6") (pin "1") (pinfunction "G_1") (pintype "passive"))
      (node (ref "R38") (pin "1") (pinfunction "1_1") (pintype "passive"))
    )
    (net (code "42") (name "Net-(Q6-S)") (class "Default")
      (node (ref "C36") (pin "1") (pinfunction "1_1") (pintype "passive"))
      (node (ref "C37") (pin "+") (pinfunction "+_+") (pintype "passive"))
      (node (ref "Q6") (pin "2") (pinfunction "S_2") (pintype "passive"))
      (node (ref "R40") (pin "2") (pinfunction "2_2") (pintype "passive"))
    )
    (net (code "43") (name "Net-(Q7-S)") (class "Default")
      (node (ref "C46") (pin "+") (pinfunction "+_+") (pintype "passive"))
      (node (ref "Q7") (pin "2") (pinfunction "S_2") (pintype "passive"))
      (node (ref "R44") (pin "2") (pinfunction "2_2") (pintype "passive"))
      (node (ref "SJ8") (pin "1") (pinfunction "1_1") (pintype "passive"))
    )
    (net (code "44") (name "Net-(Q8-B)") (class "Default")
      (node (ref "C39") (pin "2") (pinfunction "2_2") (pintype "passive"))
      (node (ref "Q8") (pin "2") (pinfunction "B_2") (pintype "passive"))
      (node (ref "R45") (pin "2") (pinfunction "2_2") (pintype "passive"))
    )
    (net (code "45") (name "Net-(Q8-E)") (class "Default")
      (node (ref "C38") (pin "2") (pinfunction "2_2") (pintype "passive"))
      (node (ref "C40") (pin "1") (pinfunction "1_1") (pintype "passive"))
      (node (ref "Q8") (pin "3") (pinfunction "E_3") (pintype "passive"))
      (node (ref "R46") (pin "1") (pinfunction "1_1") (pintype "passive"))
    )
    (net (code "46") (name "Net-(R13-Pad1)") (class "Default")
      (node (ref "R13") (pin "1") (pinfunction "1_1") (pintype "passive"))
      (node (ref "R14") (pin "2") (pinfunction "2_2") (pintype "passive"))
    )
    (net (code "47") (name "Net-(R28-Pad1)") (class "Default")
      (node (ref "R28") (pin "1") (pinfunction "1_1") (pintype "passive"))
      (node (ref "R29") (pin "2") (pinfunction "2_2") (pintype "passive"))
    )
    (net (code "48") (name "Net-(R34-Pad1)") (class "Default")
      (node (ref "R34") (pin "1") (pinfunction "1_1") (pintype "passive"))
      (node (ref "R35") (pin "2") (pinfunction "2_2") (pintype "passive"))
    )
    (net (code "49") (name "Net-(R40-Pad1)") (class "Default")
      (node (ref "R40") (pin "1") (pinfunction "1_1") (pintype "passive"))
      (node (ref "R41") (pin "2") (pinfunction "2_2") (pintype "passive"))
    )
    (net (code "50") (name "V+{slash}1") (class "Default")
      (node (ref "C3") (pin "+") (pinfunction "+_+") (pintype "passive"))
      (node (ref "C4") (pin "1") (pinfunction "1_1") (pintype "passive"))
      (node (ref "C45") (pin "1") (pinfunction "1_1") (pintype "passive"))
      (node (ref "Q1") (pin "3") (pinfunction "D_3") (pintype "passive"))
      (node (ref "Q3") (pin "3") (pinfunction "D_3") (pintype "passive"))
      (node (ref "R12") (pin "1") (pinfunction "A_1") (pintype "passive"))
      (node (ref "R2") (pin "2") (pinfunction "2_2") (pintype "passive"))
      (node (ref "R27") (pin "1") (pinfunction "A_1") (pintype "passive"))
      (node (ref "R3") (pin "1") (pinfunction "1_1") (pintype "passive"))
    )
    (net (code "51") (name "V+{slash}2") (class "Default")
      (node (ref "C1") (pin "+") (pinfunction "+_+") (pintype "passive"))
      (node (ref "C2") (pin "1") (pinfunction "1_1") (pintype "passive"))
      (node (ref "C29") (pin "1") (pinfunction "1_1") (pintype "passive"))
      (node (ref "C44") (pin "1") (pinfunction "1_1") (pintype "passive"))
      (node (ref "Q7") (pin "3") (pinfunction "D_3") (pintype "passive"))
      (node (ref "Q8") (pin "1") (pinfunction "C_1") (pintype "passive"))
      (node (ref "R1") (pin "2") (pinfunction "2_2") (pintype "passive"))
      (node (ref "R2") (pin "1") (pinfunction "1_1") (pintype "passive"))
      (node (ref "R33") (pin "1") (pinfunction "A_1") (pintype "passive"))
      (node (ref "R39") (pin "1") (pinfunction "A_1") (pintype "passive"))
      (node (ref "R43") (pin "1") (pinfunction "1_1") (pintype "passive"))
    )
    (net (code "52") (name "VCC{slash}2") (class "Default")
      (node (ref "C5") (pin "1") (pinfunction "1_1") (pintype "passive"))
      (node (ref "C6") (pin "+") (pinfunction "+_+") (pintype "passive"))
      (node (ref "R10") (pin "2") (pinfunction "2_2") (pintype "passive"))
      (node (ref "R25") (pin "2") (pinfunction "2_2") (pintype "passive"))
      (node (ref "R26") (pin "2") (pinfunction "2_2") (pintype "passive"))
      (node (ref "R3") (pin "2") (pinfunction "2_2") (pintype "passive"))
      (node (ref "R4") (pin "1") (pinfunction "1_1") (pintype "passive"))
      (node (ref "R9") (pin "2") (pinfunction "2_2") (pintype "passive"))
    )
  )
)
